# MainBoard_V5.net
KiCad netlist of a schematic drawn in EAGLE
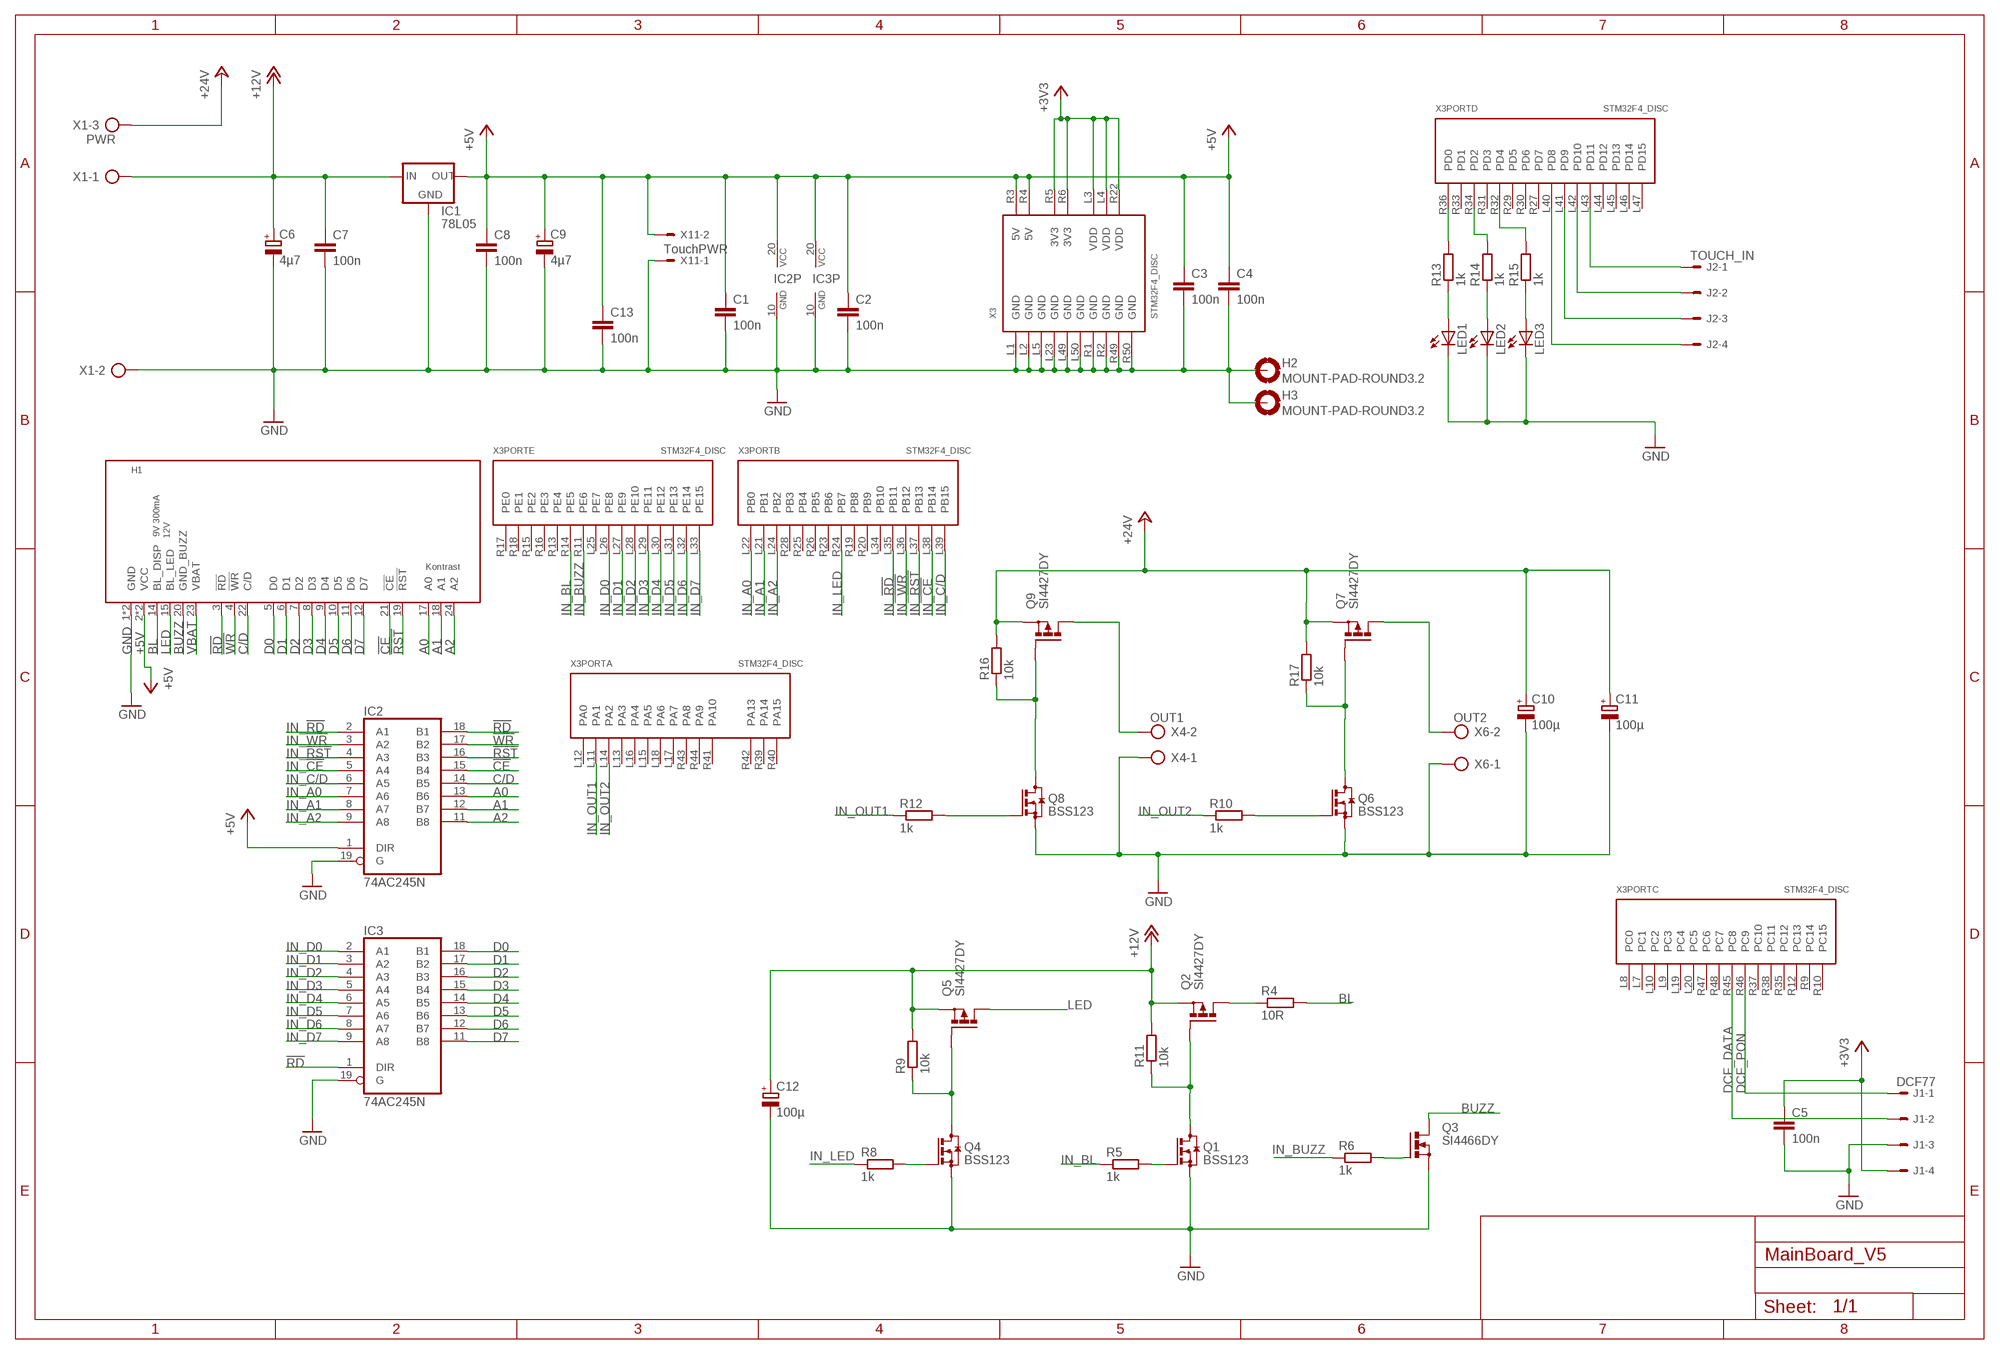
[diagram p0: schematic, sheet 1]

(export (version "E")
  (design (tool "Eeschema 10.0.6"))
  (components
    (comp (ref "C1")
      (value "100n")
      (footprint "eagle-import:C1206")
      (libsource (lib "eagle-import") (part "C-EUC1206"))
    )
    (comp (ref "C2")
      (value "100n")
      (footprint "eagle-import:C1206")
      (libsource (lib "eagle-import") (part "C-EUC1206"))
    )
    (comp (ref "C3")
      (value "100n")
      (footprint "eagle-import:C1206")
      (libsource (lib "eagle-import") (part "C-EUC1206"))
    )
    (comp (ref "C4")
      (value "100n")
      (footprint "eagle-import:C1206")
      (libsource (lib "eagle-import") (part "C-EUC1206"))
    )
    (comp (ref "C5")
      (value "100n")
      (footprint "eagle-import:C1206")
      (libsource (lib "eagle-import") (part "C-EUC1206"))
    )
    (comp (ref "C6")
      (value "4µ7")
      (footprint "eagle-import:E2-5")
      (libsource (lib "eagle-import") (part "CPOL-EUE2-5"))
    )
    (comp (ref "C7")
      (value "100n")
      (footprint "eagle-import:C1206")
      (libsource (lib "eagle-import") (part "C-EUC1206"))
    )
    (comp (ref "C8")
      (value "100n")
      (footprint "eagle-import:C1206")
      (libsource (lib "eagle-import") (part "C-EUC1206"))
    )
    (comp (ref "C9")
      (value "4µ7")
      (footprint "eagle-import:E2-5")
      (libsource (lib "eagle-import") (part "CPOL-EUE2-5"))
    )
    (comp (ref "C10")
      (value "100µ")
      (footprint "eagle-import:E2-5")
      (libsource (lib "eagle-import") (part "CPOL-EUE2-5"))
    )
    (comp (ref "C11")
      (value "100µ")
      (footprint "eagle-import:E2-5")
      (libsource (lib "eagle-import") (part "CPOL-EUE2-5"))
    )
    (comp (ref "C12")
      (value "100µ")
      (footprint "eagle-import:E2-5")
      (libsource (lib "eagle-import") (part "CPOL-EUE2-5"))
    )
    (comp (ref "C13")
      (value "100n")
      (footprint "eagle-import:C1206")
      (libsource (lib "eagle-import") (part "C-EUC1206"))
    )
    (comp (ref "H1")
      (value "YL_24012-70-MICROMATCH")
      (footprint "eagle-import:YL24012-70-MICROMATCH")
      (libsource (lib "eagle-import") (part "YL_24012-70-MICROMATCH"))
    )
    (comp (ref "H2")
      (value "MOUNT-PAD-ROUND3.2")
      (footprint "eagle-import:3,2-PAD")
      (libsource (lib "eagle-import") (part "MOUNT-PAD-ROUND3.2"))
    )
    (comp (ref "H3")
      (value "MOUNT-PAD-ROUND3.2")
      (footprint "eagle-import:3,2-PAD")
      (libsource (lib "eagle-import") (part "MOUNT-PAD-ROUND3.2"))
    )
    (comp (ref "IC1")
      (value "78L05")
      (footprint "eagle-import:78XXS")
      (libsource (lib "eagle-import") (part "78XXS"))
    )
    (comp (ref "IC2")
      (value "74AC245N")
      (footprint "eagle-import:DIL20")
      (libsource (lib "eagle-import") (part "74245NAC"))
    )
    (comp (ref "IC3")
      (value "74AC245N")
      (footprint "eagle-import:DIL20")
      (libsource (lib "eagle-import") (part "74245NAC"))
    )
    (comp (ref "J1")
      (value "DCF77")
      (footprint "eagle-import:6410-04")
      (libsource (lib "eagle-import") (part "22-?-0427-2041"))
    )
    (comp (ref "J2")
      (value "TOUCH_IN")
      (footprint "eagle-import:6410-04")
      (libsource (lib "eagle-import") (part "22-?-0427-2041"))
    )
    (comp (ref "LED1")
      (value "LED3MM")
      (footprint "eagle-import:LED3MM")
      (libsource (lib "eagle-import") (part "LED3MM"))
    )
    (comp (ref "LED2")
      (value "LED3MM")
      (footprint "eagle-import:LED3MM")
      (libsource (lib "eagle-import") (part "LED3MM"))
    )
    (comp (ref "LED3")
      (value "LED3MM")
      (footprint "eagle-import:LED3MM")
      (libsource (lib "eagle-import") (part "LED3MM"))
    )
    (comp (ref "Q1")
      (value "BSS123")
      (footprint "eagle-import:SOT23")
      (libsource (lib "eagle-import") (part "BSS123"))
    )
    (comp (ref "Q2")
      (value "SI4427DY")
      (footprint "eagle-import:SO-08")
      (libsource (lib "eagle-import") (part "P-MOSFET-SO8"))
    )
    (comp (ref "Q3")
      (value "SI4466DY")
      (footprint "eagle-import:SO-08")
      (libsource (lib "eagle-import") (part "N-MOSFET-SO8S"))
    )
    (comp (ref "Q4")
      (value "BSS123")
      (footprint "eagle-import:SOT23")
      (libsource (lib "eagle-import") (part "BSS123"))
    )
    (comp (ref "Q5")
      (value "SI4427DY")
      (footprint "eagle-import:SO-08")
      (libsource (lib "eagle-import") (part "P-MOSFET-SO8"))
    )
    (comp (ref "Q6")
      (value "BSS123")
      (footprint "eagle-import:SOT23")
      (libsource (lib "eagle-import") (part "BSS123"))
    )
    (comp (ref "Q7")
      (value "SI4427DY")
      (footprint "eagle-import:SO-08")
      (libsource (lib "eagle-import") (part "P-MOSFET-SO8"))
    )
    (comp (ref "Q8")
      (value "BSS123")
      (footprint "eagle-import:SOT23")
      (libsource (lib "eagle-import") (part "BSS123"))
    )
    (comp (ref "Q9")
      (value "SI4427DY")
      (footprint "eagle-import:SO-08")
      (libsource (lib "eagle-import") (part "P-MOSFET-SO8"))
    )
    (comp (ref "R4")
      (value "10R")
      (footprint "eagle-import:0414_15")
      (libsource (lib "eagle-import") (part "R-EU_0414/15"))
    )
    (comp (ref "R5")
      (value "1k")
      (footprint "eagle-import:0207_10")
      (libsource (lib "eagle-import") (part "R-EU_0207/10"))
    )
    (comp (ref "R6")
      (value "1k")
      (footprint "eagle-import:R0805")
      (libsource (lib "eagle-import") (part "R-EU_R0805"))
    )
    (comp (ref "R8")
      (value "1k")
      (footprint "eagle-import:0207_10")
      (libsource (lib "eagle-import") (part "R-EU_0207/10"))
    )
    (comp (ref "R9")
      (value "10k")
      (footprint "eagle-import:0207_10")
      (libsource (lib "eagle-import") (part "R-EU_0207/10"))
    )
    (comp (ref "R10")
      (value "1k")
      (footprint "eagle-import:0207_10")
      (libsource (lib "eagle-import") (part "R-EU_0207/10"))
    )
    (comp (ref "R11")
      (value "10k")
      (footprint "eagle-import:0207_10")
      (libsource (lib "eagle-import") (part "R-EU_0207/10"))
    )
    (comp (ref "R12")
      (value "1k")
      (footprint "eagle-import:0207_10")
      (libsource (lib "eagle-import") (part "R-EU_0207/10"))
    )
    (comp (ref "R13")
      (value "1k")
      (footprint "eagle-import:0207_10")
      (libsource (lib "eagle-import") (part "R-EU_0207/10"))
    )
    (comp (ref "R14")
      (value "1k")
      (footprint "eagle-import:0207_10")
      (libsource (lib "eagle-import") (part "R-EU_0207/10"))
    )
    (comp (ref "R15")
      (value "1k")
      (footprint "eagle-import:0207_10")
      (libsource (lib "eagle-import") (part "R-EU_0207/10"))
    )
    (comp (ref "R16")
      (value "10k")
      (footprint "eagle-import:R1206")
      (libsource (lib "eagle-import") (part "R-EU_R1206"))
    )
    (comp (ref "R17")
      (value "10k")
      (footprint "eagle-import:R1206")
      (libsource (lib "eagle-import") (part "R-EU_R1206"))
    )
    (comp (ref "X1")
      (value "PWR")
      (footprint "eagle-import:AK500_3")
      (libsource (lib "eagle-import") (part "AK500/3"))
    )
    (comp (ref "X3")
      (value "STM32F4_DISC")
      (footprint "eagle-import:STM32F4_DISC")
      (libsource (lib "eagle-import") (part "STM32F4_DISC"))
    )
    (comp (ref "X4")
      (value "OUT1")
      (footprint "eagle-import:AK500_2")
      (libsource (lib "eagle-import") (part "AK500/2"))
    )
    (comp (ref "X6")
      (value "OUT2")
      (footprint "eagle-import:AK500_2")
      (libsource (lib "eagle-import") (part "AK500/2"))
    )
    (comp (ref "X11")
      (value "TouchPWR")
      (footprint "eagle-import:22-23-2021")
      (fields (field (name "MF") "MOLEX") (field (name "MPN") "22-23-2021"))
      (libsource (lib "eagle-import") (part "22-23-2021"))
    )
  )
  (nets
    (net (code "1") (name "+3V3") (class "Default")
      (node (ref "C5") (pin "1") (pinfunction "1_1") (pintype "passive"))
      (node (ref "J1") (pin "4") (pinfunction "S_4") (pintype "passive"))
      (node (ref "X3") (pin "L3") (pinfunction "VDD_L3") (pintype "power_in"))
      (node (ref "X3") (pin "L4") (pinfunction "VDD_L4") (pintype "power_in"))
      (node (ref "X3") (pin "R22") (pinfunction "VDD_R22") (pintype "power_in"))
      (node (ref "X3") (pin "R5") (pinfunction "3V3_R5") (pintype "power_in"))
      (node (ref "X3") (pin "R6") (pinfunction "3V3_R6") (pintype "power_in"))
    )
    (net (code "2") (name "+5V") (class "Default")
      (node (ref "C1") (pin "1") (pinfunction "1_1") (pintype "passive"))
      (node (ref "C13") (pin "1") (pinfunction "1_1") (pintype "passive"))
      (node (ref "C2") (pin "1") (pinfunction "1_1") (pintype "passive"))
      (node (ref "C3") (pin "1") (pinfunction "1_1") (pintype "passive"))
      (node (ref "C4") (pin "1") (pinfunction "1_1") (pintype "passive"))
      (node (ref "C8") (pin "1") (pinfunction "1_1") (pintype "passive"))
      (node (ref "C9") (pin "+") (pinfunction "+_+") (pintype "passive"))
      (node (ref "H1") (pin "16") (pinfunction "VCC_16") (pintype "power_in"))
      (node (ref "H1") (pin "2") (pinfunction "VCC_2") (pintype "power_in"))
      (node (ref "IC1") (pin "OUT") (pinfunction "OUT_OUT") (pintype "passive"))
      (node (ref "IC2") (pin "1") (pinfunction "DIR_1") (pintype "input"))
      (node (ref "IC2") (pin "20") (pinfunction "VCC_20") (pintype "power_in"))
      (node (ref "IC3") (pin "20") (pinfunction "VCC_20") (pintype "power_in"))
      (node (ref "X11") (pin "2") (pinfunction "S_2") (pintype "passive"))
      (node (ref "X3") (pin "R3") (pinfunction "5V_R3") (pintype "power_in"))
      (node (ref "X3") (pin "R4") (pinfunction "5V_R4") (pintype "power_in"))
    )
    (net (code "3") (name "+12V") (class "Default")
      (node (ref "C12") (pin "+") (pinfunction "+_+") (pintype "passive"))
      (node (ref "C6") (pin "+") (pinfunction "+_+") (pintype "passive"))
      (node (ref "C7") (pin "1") (pinfunction "1_1") (pintype "passive"))
      (node (ref "IC1") (pin "IN") (pinfunction "IN_IN") (pintype "input"))
      (node (ref "Q2") (pin "1") (pinfunction "S_1") (pintype "passive"))
      (node (ref "Q2") (pin "2") (pinfunction "S_2") (pintype "passive"))
      (node (ref "Q2") (pin "3") (pinfunction "S_3") (pintype "passive"))
      (node (ref "Q5") (pin "1") (pinfunction "S_1") (pintype "passive"))
      (node (ref "Q5") (pin "2") (pinfunction "S_2") (pintype "passive"))
      (node (ref "Q5") (pin "3") (pinfunction "S_3") (pintype "passive"))
      (node (ref "R11") (pin "2") (pinfunction "2_2") (pintype "passive"))
      (node (ref "R9") (pin "2") (pinfunction "2_2") (pintype "passive"))
      (node (ref "X1") (pin "1") (pinfunction "KL_1") (pintype "passive"))
    )
    (net (code "4") (name "+24V") (class "Default")
      (node (ref "C10") (pin "+") (pinfunction "+_+") (pintype "passive"))
      (node (ref "C11") (pin "+") (pinfunction "+_+") (pintype "passive"))
      (node (ref "Q7") (pin "1") (pinfunction "S_1") (pintype "passive"))
      (node (ref "Q7") (pin "2") (pinfunction "S_2") (pintype "passive"))
      (node (ref "Q7") (pin "3") (pinfunction "S_3") (pintype "passive"))
      (node (ref "Q9") (pin "1") (pinfunction "S_1") (pintype "passive"))
      (node (ref "Q9") (pin "2") (pinfunction "S_2") (pintype "passive"))
      (node (ref "Q9") (pin "3") (pinfunction "S_3") (pintype "passive"))
      (node (ref "R16") (pin "2") (pinfunction "2_2") (pintype "passive"))
      (node (ref "R17") (pin "2") (pinfunction "2_2") (pintype "passive"))
      (node (ref "X1") (pin "3") (pinfunction "KL_3") (pintype "passive"))
    )
    (net (code "5") (name "/A0") (class "Default")
      (node (ref "H1") (pin "17") (pinfunction "A0_17") (pintype "input"))
      (node (ref "IC2") (pin "13") (pinfunction "B6_13") (pintype "bidirectional"))
    )
    (net (code "6") (name "/A1") (class "Default")
      (node (ref "H1") (pin "18") (pinfunction "A1_18") (pintype "input"))
      (node (ref "IC2") (pin "12") (pinfunction "B7_12") (pintype "bidirectional"))
    )
    (net (code "7") (name "/A2") (class "Default")
      (node (ref "H1") (pin "24") (pinfunction "A2_24") (pintype "input"))
      (node (ref "IC2") (pin "11") (pinfunction "B8_11") (pintype "bidirectional"))
    )
    (net (code "8") (name "/BL") (class "Default")
      (node (ref "H1") (pin "14") (pinfunction "BL_DISP_14") (pintype "input"))
      (node (ref "R4") (pin "2") (pinfunction "2_2") (pintype "passive"))
    )
    (net (code "9") (name "/BUZZ") (class "Default")
      (node (ref "H1") (pin "20") (pinfunction "GND_BUZZ_20") (pintype "input"))
      (node (ref "Q3") (pin "5") (pinfunction "D_5") (pintype "passive"))
      (node (ref "Q3") (pin "6") (pinfunction "D_6") (pintype "passive"))
      (node (ref "Q3") (pin "7") (pinfunction "D_7") (pintype "passive"))
      (node (ref "Q3") (pin "8") (pinfunction "D_8") (pintype "passive"))
    )
    (net (code "10") (name "/C{slash}D") (class "Default")
      (node (ref "H1") (pin "22") (pinfunction "C/D_22") (pintype "input"))
      (node (ref "IC2") (pin "14") (pinfunction "B5_14") (pintype "bidirectional"))
    )
    (net (code "11") (name "/D0") (class "Default")
      (node (ref "H1") (pin "5") (pinfunction "D0_5") (pintype "bidirectional"))
      (node (ref "IC3") (pin "18") (pinfunction "B1_18") (pintype "bidirectional"))
    )
    (net (code "12") (name "/D1") (class "Default")
      (node (ref "H1") (pin "6") (pinfunction "D1_6") (pintype "bidirectional"))
      (node (ref "IC3") (pin "17") (pinfunction "B2_17") (pintype "bidirectional"))
    )
    (net (code "13") (name "/D2") (class "Default")
      (node (ref "H1") (pin "7") (pinfunction "D2_7") (pintype "bidirectional"))
      (node (ref "IC3") (pin "16") (pinfunction "B3_16") (pintype "bidirectional"))
    )
    (net (code "14") (name "/D3") (class "Default")
      (node (ref "H1") (pin "8") (pinfunction "D3_8") (pintype "bidirectional"))
      (node (ref "IC3") (pin "15") (pinfunction "B4_15") (pintype "bidirectional"))
    )
    (net (code "15") (name "/D4") (class "Default")
      (node (ref "H1") (pin "9") (pinfunction "D4_9") (pintype "bidirectional"))
      (node (ref "IC3") (pin "14") (pinfunction "B5_14") (pintype "bidirectional"))
    )
    (net (code "16") (name "/D5") (class "Default")
      (node (ref "H1") (pin "10") (pinfunction "D5_10") (pintype "bidirectional"))
      (node (ref "IC3") (pin "13") (pinfunction "B6_13") (pintype "bidirectional"))
    )
    (net (code "17") (name "/D6") (class "Default")
      (node (ref "H1") (pin "11") (pinfunction "D6_11") (pintype "bidirectional"))
      (node (ref "IC3") (pin "12") (pinfunction "B7_12") (pintype "bidirectional"))
    )
    (net (code "18") (name "/D7") (class "Default")
      (node (ref "H1") (pin "12") (pinfunction "D7_12") (pintype "bidirectional"))
      (node (ref "IC3") (pin "11") (pinfunction "B8_11") (pintype "bidirectional"))
    )
    (net (code "19") (name "/DCF_DATA") (class "Default")
      (node (ref "J1") (pin "2") (pinfunction "S_2") (pintype "passive"))
      (node (ref "X3") (pin "R45") (pinfunction "PC8_R45") (pintype "bidirectional"))
    )
    (net (code "20") (name "/DCF_PON") (class "Default")
      (node (ref "J1") (pin "1") (pinfunction "S_1") (pintype "passive"))
      (node (ref "X3") (pin "R46") (pinfunction "PC9_R46") (pintype "bidirectional"))
    )
    (net (code "21") (name "/IN_A0") (class "Default")
      (node (ref "IC2") (pin "7") (pinfunction "A6_7") (pintype "bidirectional"))
      (node (ref "X3") (pin "L22") (pinfunction "PB0_L22") (pintype "bidirectional"))
    )
    (net (code "22") (name "/IN_A1") (class "Default")
      (node (ref "IC2") (pin "8") (pinfunction "A7_8") (pintype "bidirectional"))
      (node (ref "X3") (pin "L21") (pinfunction "PB1_L21") (pintype "bidirectional"))
    )
    (net (code "23") (name "/IN_A2") (class "Default")
      (node (ref "IC2") (pin "9") (pinfunction "A8_9") (pintype "bidirectional"))
      (node (ref "X3") (pin "L24") (pinfunction "PB2_L24") (pintype "bidirectional"))
    )
    (net (code "24") (name "/IN_BL") (class "Default")
      (node (ref "R5") (pin "1") (pinfunction "1_1") (pintype "passive"))
      (node (ref "X3") (pin "R14") (pinfunction "PE5_R14") (pintype "bidirectional"))
    )
    (net (code "25") (name "/IN_BUZZ") (class "Default")
      (node (ref "R6") (pin "1") (pinfunction "1_1") (pintype "passive"))
      (node (ref "X3") (pin "R11") (pinfunction "PE6_R11") (pintype "bidirectional"))
    )
    (net (code "26") (name "/IN_C{slash}D") (class "Default")
      (node (ref "IC2") (pin "6") (pinfunction "A5_6") (pintype "bidirectional"))
      (node (ref "X3") (pin "L39") (pinfunction "PB15_L39") (pintype "bidirectional"))
    )
    (net (code "27") (name "/IN_D0") (class "Default")
      (node (ref "IC3") (pin "2") (pinfunction "A1_2") (pintype "bidirectional"))
      (node (ref "X3") (pin "L26") (pinfunction "PE8_L26") (pintype "bidirectional"))
    )
    (net (code "28") (name "/IN_D1") (class "Default")
      (node (ref "IC3") (pin "3") (pinfunction "A2_3") (pintype "bidirectional"))
      (node (ref "X3") (pin "L27") (pinfunction "PE9_L27") (pintype "bidirectional"))
    )
    (net (code "29") (name "/IN_D2") (class "Default")
      (node (ref "IC3") (pin "4") (pinfunction "A3_4") (pintype "bidirectional"))
      (node (ref "X3") (pin "L28") (pinfunction "PE10_L28") (pintype "bidirectional"))
    )
    (net (code "30") (name "/IN_D3") (class "Default")
      (node (ref "IC3") (pin "5") (pinfunction "A4_5") (pintype "bidirectional"))
      (node (ref "X3") (pin "L29") (pinfunction "PE11_L29") (pintype "bidirectional"))
    )
    (net (code "31") (name "/IN_D4") (class "Default")
      (node (ref "IC3") (pin "6") (pinfunction "A5_6") (pintype "bidirectional"))
      (node (ref "X3") (pin "L30") (pinfunction "PE12_L30") (pintype "bidirectional"))
    )
    (net (code "32") (name "/IN_D5") (class "Default")
      (node (ref "IC3") (pin "7") (pinfunction "A6_7") (pintype "bidirectional"))
      (node (ref "X3") (pin "L31") (pinfunction "PE13_L31") (pintype "bidirectional"))
    )
    (net (code "33") (name "/IN_D6") (class "Default")
      (node (ref "IC3") (pin "8") (pinfunction "A7_8") (pintype "bidirectional"))
      (node (ref "X3") (pin "L32") (pinfunction "PE14_L32") (pintype "bidirectional"))
    )
    (net (code "34") (name "/IN_D7") (class "Default")
      (node (ref "IC3") (pin "9") (pinfunction "A8_9") (pintype "bidirectional"))
      (node (ref "X3") (pin "L33") (pinfunction "PE15_L33") (pintype "bidirectional"))
    )
    (net (code "35") (name "/IN_LED") (class "Default")
      (node (ref "R8") (pin "1") (pinfunction "1_1") (pintype "passive"))
      (node (ref "X3") (pin "R24") (pinfunction "PB7_R24") (pintype "bidirectional"))
    )
    (net (code "36") (name "/IN_OUT1") (class "Default")
      (node (ref "R12") (pin "1") (pinfunction "1_1") (pintype "passive"))
      (node (ref "X3") (pin "L11") (pinfunction "PA1_L11") (pintype "bidirectional"))
    )
    (net (code "37") (name "/IN_OUT2") (class "Default")
      (node (ref "R10") (pin "1") (pinfunction "1_1") (pintype "passive"))
      (node (ref "X3") (pin "L14") (pinfunction "PA2_L14") (pintype "bidirectional"))
    )
    (net (code "38") (name "/IN_~{CE}") (class "Default")
      (node (ref "IC2") (pin "5") (pinfunction "A4_5") (pintype "bidirectional"))
      (node (ref "X3") (pin "L38") (pinfunction "PB14_L38") (pintype "bidirectional"))
    )
    (net (code "39") (name "/IN_~{RD}") (class "Default")
      (node (ref "IC2") (pin "2") (pinfunction "A1_2") (pintype "bidirectional"))
      (node (ref "X3") (pin "L35") (pinfunction "PB11_L35") (pintype "bidirectional"))
    )
    (net (code "40") (name "/IN_~{RST}") (class "Default")
      (node (ref "IC2") (pin "4") (pinfunction "A3_4") (pintype "bidirectional"))
      (node (ref "X3") (pin "L37") (pinfunction "PB13_L37") (pintype "bidirectional"))
    )
    (net (code "41") (name "/IN_~{WR}") (class "Default")
      (node (ref "IC2") (pin "3") (pinfunction "A2_3") (pintype "bidirectional"))
      (node (ref "X3") (pin "L36") (pinfunction "PB12_L36") (pintype "bidirectional"))
    )
    (net (code "42") (name "/LED") (class "Default")
      (node (ref "H1") (pin "15") (pinfunction "BL_LED_15") (pintype "input"))
      (node (ref "Q5") (pin "5") (pinfunction "D_5") (pintype "passive"))
      (node (ref "Q5") (pin "6") (pinfunction "D_6") (pintype "passive"))
      (node (ref "Q5") (pin "7") (pinfunction "D_7") (pintype "passive"))
      (node (ref "Q5") (pin "8") (pinfunction "D_8") (pintype "passive"))
    )
    (net (code "43") (name "/VBAT") (class "Default")
      (node (ref "H1") (pin "23") (pinfunction "VBAT_23") (pintype "output"))
    )
    (net (code "44") (name "/~{CE}") (class "Default")
      (node (ref "H1") (pin "21") (pinfunction "~{CE}_21") (pintype "input"))
      (node (ref "IC2") (pin "15") (pinfunction "B4_15") (pintype "bidirectional"))
    )
    (net (code "45") (name "/~{RD}") (class "Default")
      (node (ref "H1") (pin "3") (pinfunction "~{RD}_3") (pintype "input"))
      (node (ref "IC2") (pin "18") (pinfunction "B1_18") (pintype "bidirectional"))
      (node (ref "IC3") (pin "1") (pinfunction "DIR_1") (pintype "input"))
    )
    (net (code "46") (name "/~{RST}") (class "Default")
      (node (ref "H1") (pin "19") (pinfunction "~{RST}_19") (pintype "input"))
      (node (ref "IC2") (pin "16") (pinfunction "B3_16") (pintype "bidirectional"))
    )
    (net (code "47") (name "/~{WR}") (class "Default")
      (node (ref "H1") (pin "4") (pinfunction "~{WR}_4") (pintype "input"))
      (node (ref "IC2") (pin "17") (pinfunction "B2_17") (pintype "bidirectional"))
    )
    (net (code "48") (name "GND") (class "Default")
      (node (ref "C1") (pin "2") (pinfunction "2_2") (pintype "passive"))
      (node (ref "C10") (pin "-") (pinfunction "-_-") (pintype "passive"))
      (node (ref "C11") (pin "-") (pinfunction "-_-") (pintype "passive"))
      (node (ref "C12") (pin "-") (pinfunction "-_-") (pintype "passive"))
      (node (ref "C13") (pin "2") (pinfunction "2_2") (pintype "passive"))
      (node (ref "C2") (pin "2") (pinfunction "2_2") (pintype "passive"))
      (node (ref "C3") (pin "2") (pinfunction "2_2") (pintype "passive"))
      (node (ref "C4") (pin "2") (pinfunction "2_2") (pintype "passive"))
      (node (ref "C5") (pin "2") (pinfunction "2_2") (pintype "passive"))
      (node (ref "C6") (pin "-") (pinfunction "-_-") (pintype "passive"))
      (node (ref "C7") (pin "2") (pinfunction "2_2") (pintype "passive"))
      (node (ref "C8") (pin "2") (pinfunction "2_2") (pintype "passive"))
      (node (ref "C9") (pin "-") (pinfunction "-_-") (pintype "passive"))
      (node (ref "H1") (pin "1") (pinfunction "GND_1") (pintype "power_in"))
      (node (ref "H1") (pin "13") (pinfunction "GND_13") (pintype "power_in"))
      (node (ref "H2") (pin "B3,2") (pinfunction "MOUNT_B3,2") (pintype "passive"))
      (node (ref "H3") (pin "B3,2") (pinfunction "MOUNT_B3,2") (pintype "passive"))
      (node (ref "IC1") (pin "GND") (pinfunction "GND_GND") (pintype "input"))
      (node (ref "IC2") (pin "10") (pinfunction "GND_10") (pintype "power_in"))
      (node (ref "IC2") (pin "19") (pinfunction "G_19") (pintype "input"))
      (node (ref "IC3") (pin "10") (pinfunction "GND_10") (pintype "power_in"))
      (node (ref "IC3") (pin "19") (pinfunction "G_19") (pintype "input"))
      (node (ref "J1") (pin "3") (pinfunction "S_3") (pintype "passive"))
      (node (ref "LED1") (pin "K") (pinfunction "C_K") (pintype "passive"))
      (node (ref "LED2") (pin "K") (pinfunction "C_K") (pintype "passive"))
      (node (ref "LED3") (pin "K") (pinfunction "C_K") (pintype "passive"))
      (node (ref "Q1") (pin "2") (pinfunction "S_2") (pintype "passive"))
      (node (ref "Q3") (pin "1") (pinfunction "S_1") (pintype "passive"))
      (node (ref "Q3") (pin "2") (pinfunction "S_2") (pintype "passive"))
      (node (ref "Q3") (pin "3") (pinfunction "S_3") (pintype "passive"))
      (node (ref "Q4") (pin "2") (pinfunction "S_2") (pintype "passive"))
      (node (ref "Q6") (pin "2") (pinfunction "S_2") (pintype "passive"))
      (node (ref "Q8") (pin "2") (pinfunction "S_2") (pintype "passive"))
      (node (ref "X1") (pin "2") (pinfunction "KL_2") (pintype "passive"))
      (node (ref "X11") (pin "1") (pinfunction "S_1") (pintype "passive"))
      (node (ref "X3") (pin "L1") (pinfunction "GND_L1") (pintype "power_in"))
      (node (ref "X3") (pin "L2") (pinfunction "GND_L2") (pintype "power_in"))
      (node (ref "X3") (pin "L23") (pinfunction "GND_L23") (pintype "power_in"))
      (node (ref "X3") (pin "L49") (pinfunction "GND_L49") (pintype "power_in"))
      (node (ref "X3") (pin "L5") (pinfunction "GND_L5") (pintype "power_in"))
      (node (ref "X3") (pin "L50") (pinfunction "GND_L50") (pintype "power_in"))
      (node (ref "X3") (pin "R1") (pinfunction "GND_R1") (pintype "power_in"))
      (node (ref "X3") (pin "R2") (pinfunction "GND_R2") (pintype "power_in"))
      (node (ref "X3") (pin "R49") (pinfunction "GND_R49") (pintype "power_in"))
      (node (ref "X3") (pin "R50") (pinfunction "GND_R50") (pintype "power_in"))
      (node (ref "X4") (pin "1") (pinfunction "KL_1") (pintype "passive"))
      (node (ref "X6") (pin "1") (pinfunction "KL_1") (pintype "passive"))
    )
    (net (code "49") (name "Net-(J2A-S)") (class "Default")
      (node (ref "J2") (pin "1") (pinfunction "S_1") (pintype "passive"))
      (node (ref "X3") (pin "L43") (pinfunction "PD11_L43") (pintype "bidirectional"))
    )
    (net (code "50") (name "Net-(J2B-S)") (class "Default")
      (node (ref "J2") (pin "2") (pinfunction "S_2") (pintype "passive"))
      (node (ref "X3") (pin "L42") (pinfunction "PD10_L42") (pintype "bidirectional"))
    )
    (net (code "51") (name "Net-(J2C-S)") (class "Default")
      (node (ref "J2") (pin "3") (pinfunction "S_3") (pintype "passive"))
      (node (ref "X3") (pin "L41") (pinfunction "PD9_L41") (pintype "bidirectional"))
    )
    (net (code "52") (name "Net-(J2D-S)") (class "Default")
      (node (ref "J2") (pin "4") (pinfunction "S_4") (pintype "passive"))
      (node (ref "X3") (pin "L40") (pinfunction "PD8_L40") (pintype "bidirectional"))
    )
    (net (code "53") (name "Net-(LED1-PadA)") (class "Default")
      (node (ref "LED1") (pin "A") (pinfunction "A_A") (pintype "passive"))
      (node (ref "R13") (pin "1") (pinfunction "1_1") (pintype "passive"))
    )
    (net (code "54") (name "Net-(LED2-PadA)") (class "Default")
      (node (ref "LED2") (pin "A") (pinfunction "A_A") (pintype "passive"))
      (node (ref "R14") (pin "1") (pinfunction "1_1") (pintype "passive"))
    )
    (net (code "55") (name "Net-(LED3-PadA)") (class "Default")
      (node (ref "LED3") (pin "A") (pinfunction "A_A") (pintype "passive"))
      (node (ref "R15") (pin "1") (pinfunction "1_1") (pintype "passive"))
    )
    (net (code "56") (name "Net-(Q1-D)") (class "Default")
      (node (ref "Q1") (pin "3") (pinfunction "D_3") (pintype "passive"))
      (node (ref "Q2") (pin "4") (pinfunction "G_4") (pintype "passive"))
      (node (ref "R11") (pin "1") (pinfunction "1_1") (pintype "passive"))
    )
    (net (code "57") (name "Net-(Q1-G)") (class "Default")
      (node (ref "Q1") (pin "1") (pinfunction "G_1") (pintype "passive"))
      (node (ref "R5") (pin "2") (pinfunction "2_2") (pintype "passive"))
    )
    (net (code "58") (name "Net-(Q2-D-Pad5)") (class "Default")
      (node (ref "Q2") (pin "5") (pinfunction "D_5") (pintype "passive"))
      (node (ref "Q2") (pin "6") (pinfunction "D_6") (pintype "passive"))
      (node (ref "Q2") (pin "7") (pinfunction "D_7") (pintype "passive"))
      (node (ref "Q2") (pin "8") (pinfunction "D_8") (pintype "passive"))
      (node (ref "R4") (pin "1") (pinfunction "1_1") (pintype "passive"))
    )
    (net (code "59") (name "Net-(Q3-G)") (class "Default")
      (node (ref "Q3") (pin "4") (pinfunction "G_4") (pintype "passive"))
      (node (ref "R6") (pin "2") (pinfunction "2_2") (pintype "passive"))
    )
    (net (code "60") (name "Net-(Q4-D)") (class "Default")
      (node (ref "Q4") (pin "3") (pinfunction "D_3") (pintype "passive"))
      (node (ref "Q5") (pin "4") (pinfunction "G_4") (pintype "passive"))
      (node (ref "R9") (pin "1") (pinfunction "1_1") (pintype "passive"))
    )
    (net (code "61") (name "Net-(Q4-G)") (class "Default")
      (node (ref "Q4") (pin "1") (pinfunction "G_1") (pintype "passive"))
      (node (ref "R8") (pin "2") (pinfunction "2_2") (pintype "passive"))
    )
    (net (code "62") (name "Net-(Q6-D)") (class "Default")
      (node (ref "Q6") (pin "3") (pinfunction "D_3") (pintype "passive"))
      (node (ref "Q7") (pin "4") (pinfunction "G_4") (pintype "passive"))
      (node (ref "R17") (pin "1") (pinfunction "1_1") (pintype "passive"))
    )
    (net (code "63") (name "Net-(Q6-G)") (class "Default")
      (node (ref "Q6") (pin "1") (pinfunction "G_1") (pintype "passive"))
      (node (ref "R10") (pin "2") (pinfunction "2_2") (pintype "passive"))
    )
    (net (code "64") (name "Net-(Q8-D)") (class "Default")
      (node (ref "Q8") (pin "3") (pinfunction "D_3") (pintype "passive"))
      (node (ref "Q9") (pin "4") (pinfunction "G_4") (pintype "passive"))
      (node (ref "R16") (pin "1") (pinfunction "1_1") (pintype "passive"))
    )
    (net (code "65") (name "Net-(Q8-G)") (class "Default")
      (node (ref "Q8") (pin "1") (pinfunction "G_1") (pintype "passive"))
      (node (ref "R12") (pin "2") (pinfunction "2_2") (pintype "passive"))
    )
    (net (code "66") (name "Net-(X3D-PD0)") (class "Default")
      (node (ref "R13") (pin "2") (pinfunction "2_2") (pintype "passive"))
      (node (ref "X3") (pin "R36") (pinfunction "PD0_R36") (pintype "bidirectional"))
    )
    (net (code "67") (name "Net-(X3D-PD2)") (class "Default")
      (node (ref "R14") (pin "2") (pinfunction "2_2") (pintype "passive"))
      (node (ref "X3") (pin "R34") (pinfunction "PD2_R34") (pintype "bidirectional"))
    )
    (net (code "68") (name "Net-(X3D-PD4)") (class "Default")
      (node (ref "R15") (pin "2") (pinfunction "2_2") (pintype "passive"))
      (node (ref "X3") (pin "R32") (pinfunction "PD4_R32") (pintype "bidirectional"))
    )
    (net (code "69") (name "Net-(X4B-KL)") (class "Default")
      (node (ref "Q9") (pin "5") (pinfunction "D_5") (pintype "passive"))
      (node (ref "Q9") (pin "6") (pinfunction "D_6") (pintype "passive"))
      (node (ref "Q9") (pin "7") (pinfunction "D_7") (pintype "passive"))
      (node (ref "Q9") (pin "8") (pinfunction "D_8") (pintype "passive"))
      (node (ref "X4") (pin "2") (pinfunction "KL_2") (pintype "passive"))
    )
    (net (code "70") (name "Net-(X6B-KL)") (class "Default")
      (node (ref "Q7") (pin "5") (pinfunction "D_5") (pintype "passive"))
      (node (ref "Q7") (pin "6") (pinfunction "D_6") (pintype "passive"))
      (node (ref "Q7") (pin "7") (pinfunction "D_7") (pintype "passive"))
      (node (ref "Q7") (pin "8") (pinfunction "D_8") (pintype "passive"))
      (node (ref "X6") (pin "2") (pinfunction "KL_2") (pintype "passive"))
    )
    (net (code "71") (name "unconnected-(X3A-PA0-PadL12)") (class "Default")
      (node (ref "X3") (pin "L12") (pinfunction "PA0_L12") (pintype "bidirectional"))
    )
    (net (code "72") (name "unconnected-(X3A-PA3-PadL13)") (class "Default")
      (node (ref "X3") (pin "L13") (pinfunction "PA3_L13") (pintype "bidirectional"))
    )
    (net (code "73") (name "unconnected-(X3A-PA4-PadL16)") (class "Default")
      (node (ref "X3") (pin "L16") (pinfunction "PA4_L16") (pintype "bidirectional"))
    )
    (net (code "74") (name "unconnected-(X3A-PA5-PadL15)") (class "Default")
      (node (ref "X3") (pin "L15") (pinfunction "PA5_L15") (pintype "bidirectional"))
    )
    (net (code "75") (name "unconnected-(X3A-PA6-PadL18)") (class "Default")
      (node (ref "X3") (pin "L18") (pinfunction "PA6_L18") (pintype "bidirectional"))
    )
    (net (code "76") (name "unconnected-(X3A-PA7-PadL17)") (class "Default")
      (node (ref "X3") (pin "L17") (pinfunction "PA7_L17") (pintype "bidirectional"))
    )
    (net (code "77") (name "unconnected-(X3A-PA8-PadR43)") (class "Default")
      (node (ref "X3") (pin "R43") (pinfunction "PA8_R43") (pintype "bidirectional"))
    )
    (net (code "78") (name "unconnected-(X3A-PA9-PadR44)") (class "Default")
      (node (ref "X3") (pin "R44") (pinfunction "PA9_R44") (pintype "bidirectional"))
    )
    (net (code "79") (name "unconnected-(X3A-PA10-PadR41)") (class "Default")
      (node (ref "X3") (pin "R41") (pinfunction "PA10_R41") (pintype "bidirectional"))
    )
    (net (code "80") (name "unconnected-(X3A-PA13-PadR42)") (class "Default")
      (node (ref "X3") (pin "R42") (pinfunction "PA13_R42") (pintype "bidirectional"))
    )
    (net (code "81") (name "unconnected-(X3A-PA14-PadR39)") (class "Default")
      (node (ref "X3") (pin "R39") (pinfunction "PA14_R39") (pintype "bidirectional"))
    )
    (net (code "82") (name "unconnected-(X3A-PA15-PadR40)") (class "Default")
      (node (ref "X3") (pin "R40") (pinfunction "PA15_R40") (pintype "bidirectional"))
    )
    (net (code "83") (name "unconnected-(X3B-PB3-PadR28)") (class "Default")
      (node (ref "X3") (pin "R28") (pinfunction "PB3_R28") (pintype "bidirectional"))
    )
    (net (code "84") (name "unconnected-(X3B-PB4-PadR25)") (class "Default")
      (node (ref "X3") (pin "R25") (pinfunction "PB4_R25") (pintype "bidirectional"))
    )
    (net (code "85") (name "unconnected-(X3B-PB5-PadR26)") (class "Default")
      (node (ref "X3") (pin "R26") (pinfunction "PB5_R26") (pintype "bidirectional"))
    )
    (net (code "86") (name "unconnected-(X3B-PB6-PadR23)") (class "Default")
      (node (ref "X3") (pin "R23") (pinfunction "PB6_R23") (pintype "bidirectional"))
    )
    (net (code "87") (name "unconnected-(X3B-PB8-PadR19)") (class "Default")
      (node (ref "X3") (pin "R19") (pinfunction "PB8_R19") (pintype "bidirectional"))
    )
    (net (code "88") (name "unconnected-(X3B-PB9-PadR20)") (class "Default")
      (node (ref "X3") (pin "R20") (pinfunction "PB9_R20") (pintype "bidirectional"))
    )
    (net (code "89") (name "unconnected-(X3B-PB10-PadL34)") (class "Default")
      (node (ref "X3") (pin "L34") (pinfunction "PB10_L34") (pintype "bidirectional"))
    )
    (net (code "90") (name "unconnected-(X3C-PC0-PadL8)") (class "Default")
      (node (ref "X3") (pin "L8") (pinfunction "PC0_L8") (pintype "bidirectional"))
    )
    (net (code "91") (name "unconnected-(X3C-PC1-PadL7)") (class "Default")
      (node (ref "X3") (pin "L7") (pinfunction "PC1_L7") (pintype "bidirectional"))
    )
    (net (code "92") (name "unconnected-(X3C-PC2-PadL10)") (class "Default")
      (node (ref "X3") (pin "L10") (pinfunction "PC2_L10") (pintype "bidirectional"))
    )
    (net (code "93") (name "unconnected-(X3C-PC3-PadL9)") (class "Default")
      (node (ref "X3") (pin "L9") (pinfunction "PC3_L9") (pintype "bidirectional"))
    )
    (net (code "94") (name "unconnected-(X3C-PC4-PadL19)") (class "Default")
      (node (ref "X3") (pin "L19") (pinfunction "PC4_L19") (pintype "bidirectional"))
    )
    (net (code "95") (name "unconnected-(X3C-PC5-PadL20)") (class "Default")
      (node (ref "X3") (pin "L20") (pinfunction "PC5_L20") (pintype "bidirectional"))
    )
    (net (code "96") (name "unconnected-(X3C-PC6-PadR47)") (class "Default")
      (node (ref "X3") (pin "R47") (pinfunction "PC6_R47") (pintype "bidirectional"))
    )
    (net (code "97") (name "unconnected-(X3C-PC7-PadR48)") (class "Default")
      (node (ref "X3") (pin "R48") (pinfunction "PC7_R48") (pintype "bidirectional"))
    )
    (net (code "98") (name "unconnected-(X3C-PC10-PadR37)") (class "Default")
      (node (ref "X3") (pin "R37") (pinfunction "PC10_R37") (pintype "bidirectional"))
    )
    (net (code "99") (name "unconnected-(X3C-PC11-PadR38)") (class "Default")
      (node (ref "X3") (pin "R38") (pinfunction "PC11_R38") (pintype "bidirectional"))
    )
    (net (code "100") (name "unconnected-(X3C-PC12-PadR35)") (class "Default")
      (node (ref "X3") (pin "R35") (pinfunction "PC12_R35") (pintype "bidirectional"))
    )
    (net (code "101") (name "unconnected-(X3C-PC13-PadR12)") (class "Default")
      (node (ref "X3") (pin "R12") (pinfunction "PC13_R12") (pintype "bidirectional"))
    )
    (net (code "102") (name "unconnected-(X3C-PC14-PadR9)") (class "Default")
      (node (ref "X3") (pin "R9") (pinfunction "PC14_R9") (pintype "bidirectional"))
    )
    (net (code "103") (name "unconnected-(X3C-PC15-PadR10)") (class "Default")
      (node (ref "X3") (pin "R10") (pinfunction "PC15_R10") (pintype "bidirectional"))
    )
    (net (code "104") (name "unconnected-(X3D-PD1-PadR33)") (class "Default")
      (node (ref "X3") (pin "R33") (pinfunction "PD1_R33") (pintype "bidirectional"))
    )
    (net (code "105") (name "unconnected-(X3D-PD3-PadR31)") (class "Default")
      (node (ref "X3") (pin "R31") (pinfunction "PD3_R31") (pintype "bidirectional"))
    )
    (net (code "106") (name "unconnected-(X3D-PD5-PadR29)") (class "Default")
      (node (ref "X3") (pin "R29") (pinfunction "PD5_R29") (pintype "bidirectional"))
    )
    (net (code "107") (name "unconnected-(X3D-PD6-PadR30)") (class "Default")
      (node (ref "X3") (pin "R30") (pinfunction "PD6_R30") (pintype "bidirectional"))
    )
    (net (code "108") (name "unconnected-(X3D-PD7-PadR27)") (class "Default")
      (node (ref "X3") (pin "R27") (pinfunction "PD7_R27") (pintype "bidirectional"))
    )
    (net (code "109") (name "unconnected-(X3D-PD12-PadL44)") (class "Default")
      (node (ref "X3") (pin "L44") (pinfunction "PD12_L44") (pintype "bidirectional"))
    )
    (net (code "110") (name "unconnected-(X3D-PD13-PadL45)") (class "Default")
      (node (ref "X3") (pin "L45") (pinfunction "PD13_L45") (pintype "bidirectional"))
    )
    (net (code "111") (name "unconnected-(X3D-PD14-PadL46)") (class "Default")
      (node (ref "X3") (pin "L46") (pinfunction "PD14_L46") (pintype "bidirectional"))
    )
    (net (code "112") (name "unconnected-(X3D-PD15-PadL47)") (class "Default")
      (node (ref "X3") (pin "L47") (pinfunction "PD15_L47") (pintype "bidirectional"))
    )
    (net (code "113") (name "unconnected-(X3E-PE0-PadR17)") (class "Default")
      (node (ref "X3") (pin "R17") (pinfunction "PE0_R17") (pintype "bidirectional"))
    )
    (net (code "114") (name "unconnected-(X3E-PE1-PadR18)") (class "Default")
      (node (ref "X3") (pin "R18") (pinfunction "PE1_R18") (pintype "bidirectional"))
    )
    (net (code "115") (name "unconnected-(X3E-PE2-PadR15)") (class "Default")
      (node (ref "X3") (pin "R15") (pinfunction "PE2_R15") (pintype "bidirectional"))
    )
    (net (code "116") (name "unconnected-(X3E-PE3-PadR16)") (class "Default")
      (node (ref "X3") (pin "R16") (pinfunction "PE3_R16") (pintype "bidirectional"))
    )
    (net (code "117") (name "unconnected-(X3E-PE4-PadR13)") (class "Default")
      (node (ref "X3") (pin "R13") (pinfunction "PE4_R13") (pintype "bidirectional"))
    )
    (net (code "118") (name "unconnected-(X3E-PE7-PadL25)") (class "Default")
      (node (ref "X3") (pin "L25") (pinfunction "PE7_L25") (pintype "bidirectional"))
    )
  )
)
